# ADSR_Waveform_v1_05.net
KiCad netlist of a schematic drawn in EAGLE
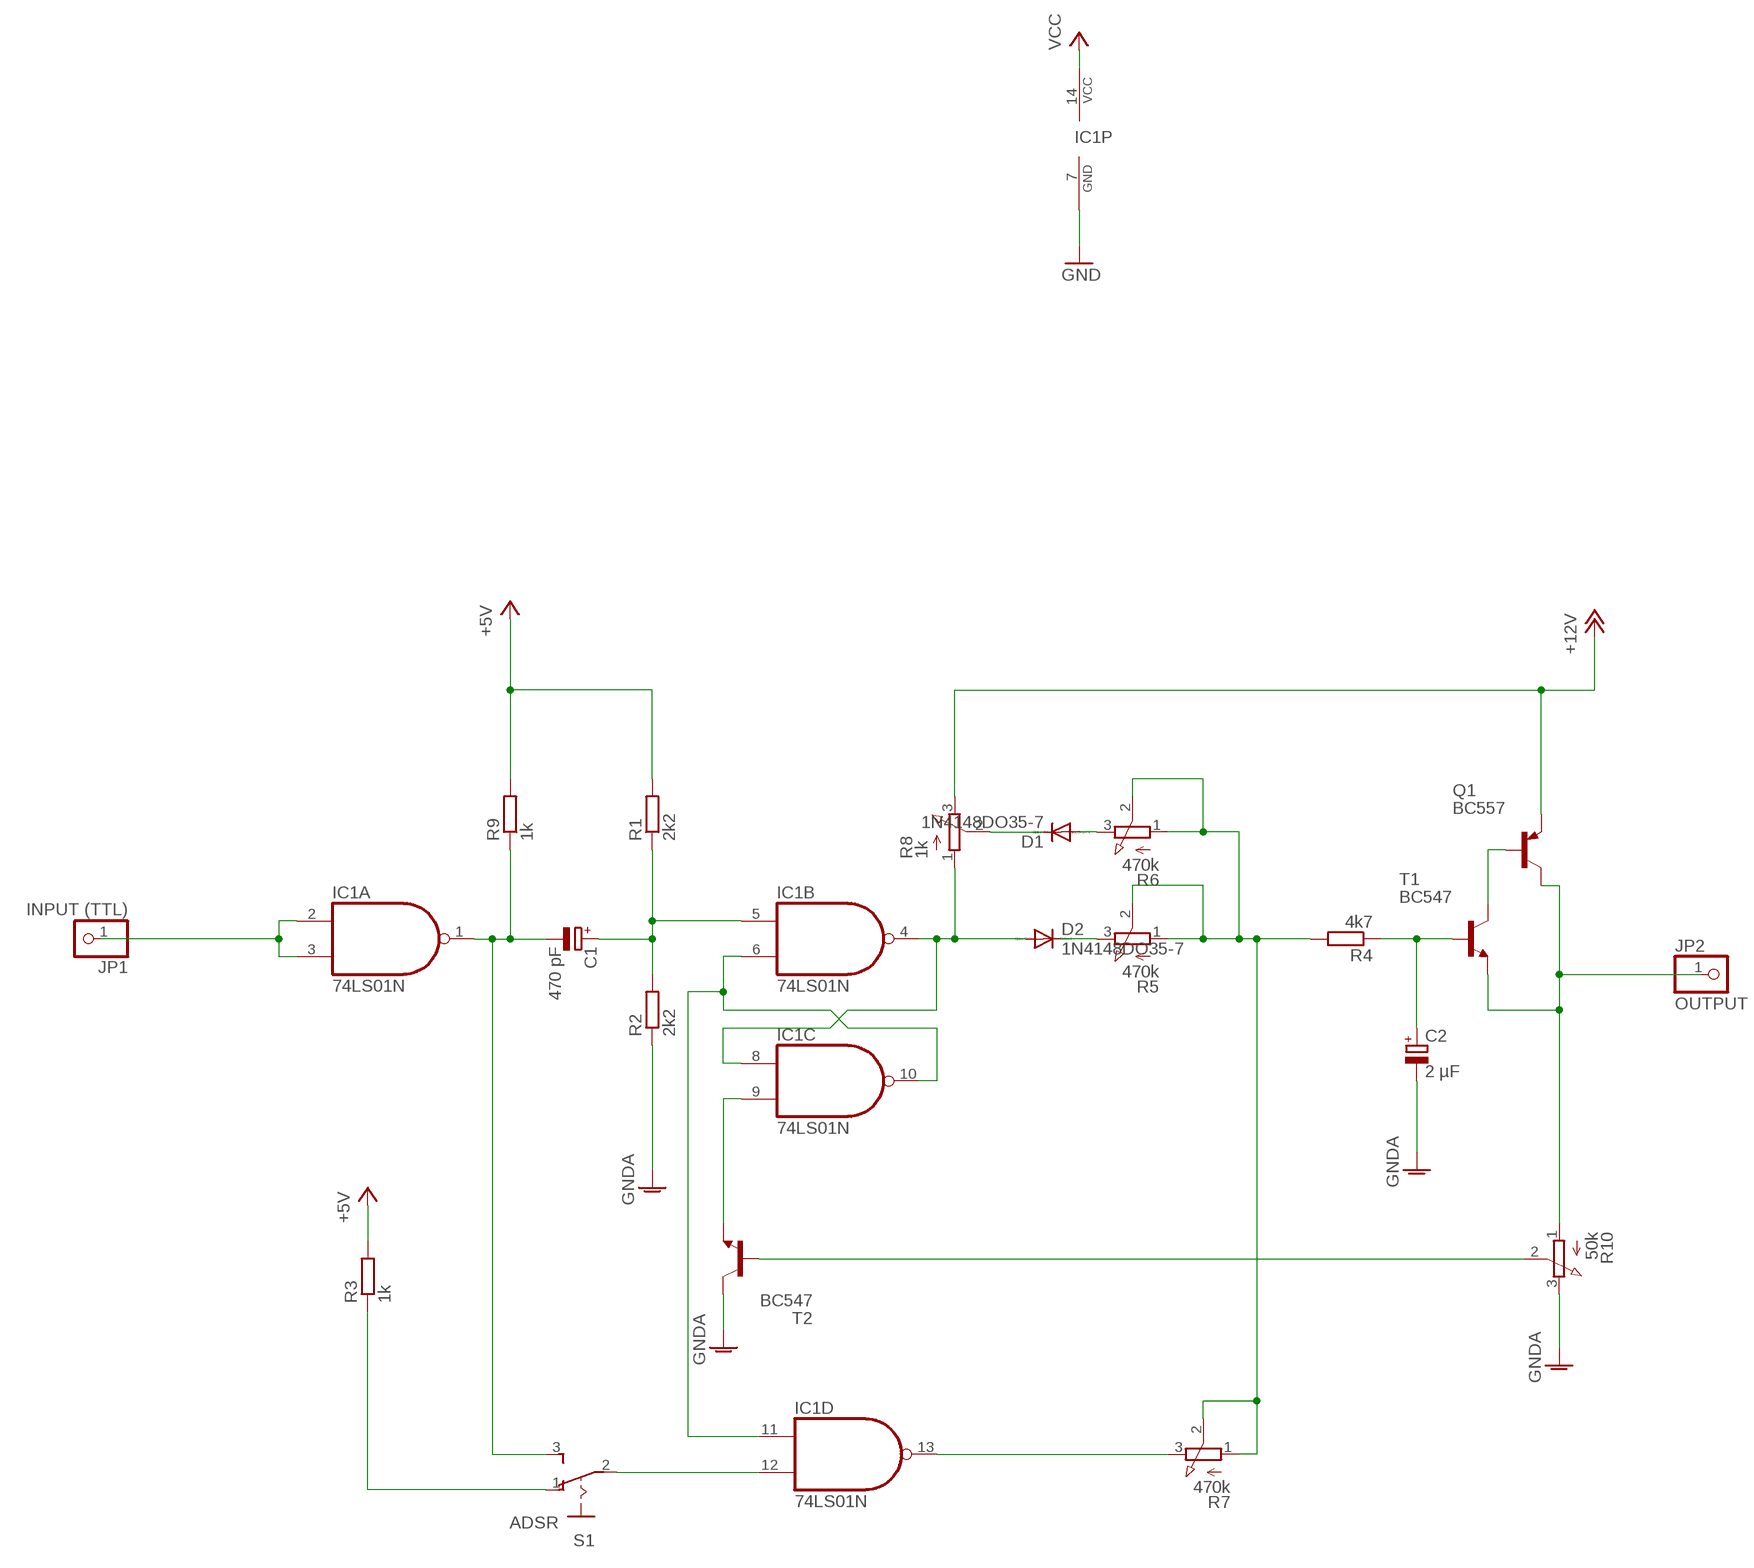
[diagram p0: schematic, sheet 1]

(export (version "E")
  (design (tool "Eeschema 10.0.6"))
  (components
    (comp (ref "C1")
      (value "470 pF")
      (footprint "eagle-import:E5-5")
      (libsource (lib "eagle-import") (part "CPOL-EUE5-5"))
    )
    (comp (ref "C2")
      (value "2 µF")
      (footprint "eagle-import:E5-5")
      (libsource (lib "eagle-import") (part "CPOL-EUE5-5"))
    )
    (comp (ref "D1")
      (value "1N4148DO35-7")
      (footprint "eagle-import:DO35-7")
      (libsource (lib "eagle-import") (part "1N4148DO35-7"))
    )
    (comp (ref "D2")
      (value "1N4148DO35-7")
      (footprint "eagle-import:DO35-7")
      (libsource (lib "eagle-import") (part "1N4148DO35-7"))
    )
    (comp (ref "IC1")
      (value "74LS01N")
      (footprint "eagle-import:DIL14")
      (libsource (lib "eagle-import") (part "7401NLS"))
    )
    (comp (ref "JP1")
      (value "INPUT (TTL)")
      (footprint "eagle-import:1X01")
      (libsource (lib "eagle-import") (part "PINHD-1X1"))
    )
    (comp (ref "JP2")
      (value "OUTPUT")
      (footprint "eagle-import:1X01")
      (libsource (lib "eagle-import") (part "PINHD-1X1"))
    )
    (comp (ref "Q1")
      (value "BC557")
      (footprint "eagle-import:TO92")
      (libsource (lib "eagle-import") (part "BC557"))
    )
    (comp (ref "R1")
      (value "2k2")
      (footprint "eagle-import:0204_5")
      (libsource (lib "eagle-import") (part "R-EU_0204/5"))
    )
    (comp (ref "R2")
      (value "2k2")
      (footprint "eagle-import:0204_5")
      (libsource (lib "eagle-import") (part "R-EU_0204/5"))
    )
    (comp (ref "R3")
      (value "1k")
      (footprint "eagle-import:0204_5")
      (libsource (lib "eagle-import") (part "R-EU_0204/5"))
    )
    (comp (ref "R4")
      (value "4k7")
      (footprint "eagle-import:0204_5")
      (libsource (lib "eagle-import") (part "R-EU_0204/5"))
    )
    (comp (ref "R5")
      (value "470k")
      (footprint "eagle-import:3RP_1610N")
      (libsource (lib "eagle-import") (part "3RP/1610N"))
    )
    (comp (ref "R6")
      (value "470k")
      (footprint "eagle-import:3RP_1610N")
      (libsource (lib "eagle-import") (part "3RP/1610N"))
    )
    (comp (ref "R7")
      (value "470k")
      (footprint "eagle-import:3RP_1610N")
      (libsource (lib "eagle-import") (part "3RP/1610N"))
    )
    (comp (ref "R8")
      (value "1k")
      (footprint "eagle-import:3RP_1610N")
      (libsource (lib "eagle-import") (part "3RP/1610N"))
    )
    (comp (ref "R9")
      (value "1k")
      (footprint "eagle-import:0204_5")
      (libsource (lib "eagle-import") (part "R-EU_0204/5"))
    )
    (comp (ref "R10")
      (value "50k")
      (footprint "eagle-import:3RP_1610N")
      (libsource (lib "eagle-import") (part "3RP/1610N"))
    )
    (comp (ref "S1")
      (value "ADSR")
      (footprint "eagle-import:255SB")
      (libsource (lib "eagle-import") (part "255SB"))
    )
    (comp (ref "T1")
      (value "BC547")
      (footprint "eagle-import:TO92")
      (libsource (lib "eagle-import") (part "BC547"))
    )
    (comp (ref "T2")
      (value "BC547")
      (footprint "eagle-import:TO92")
      (libsource (lib "eagle-import") (part "BC547"))
    )
  )
  (nets
    (net (code "1") (name "+5V") (class "Default")
      (node (ref "R1") (pin "2") (pinfunction "2_2") (pintype "passive"))
      (node (ref "R3") (pin "2") (pinfunction "2_2") (pintype "passive"))
      (node (ref "R9") (pin "2") (pinfunction "2_2") (pintype "passive"))
    )
    (net (code "2") (name "+12V") (class "Default")
      (node (ref "Q1") (pin "1") (pinfunction "E_1") (pintype "passive"))
      (node (ref "R8") (pin "3") (pinfunction "E_3") (pintype "passive"))
    )
    (net (code "3") (name "GND") (class "Default")
      (node (ref "IC1") (pin "7") (pinfunction "GND_7") (pintype "power_in"))
    )
    (net (code "4") (name "GNDA") (class "Default")
      (node (ref "C2") (pin "-") (pinfunction "-_-") (pintype "passive"))
      (node (ref "R10") (pin "3") (pinfunction "E_3") (pintype "passive"))
      (node (ref "R2") (pin "1") (pinfunction "1_1") (pintype "passive"))
      (node (ref "T2") (pin "3") (pinfunction "C_3") (pintype "passive"))
    )
    (net (code "5") (name "Net-(IC1A-I0)") (class "Default")
      (node (ref "IC1") (pin "2") (pinfunction "I0_2") (pintype "input"))
      (node (ref "IC1") (pin "3") (pinfunction "I1_3") (pintype "input"))
      (node (ref "JP1") (pin "1") (pinfunction "1_1") (pintype "passive"))
    )
    (net (code "6") (name "Net-(IC1A-O)") (class "Default")
      (node (ref "C1") (pin "-") (pinfunction "-_-") (pintype "passive"))
      (node (ref "IC1") (pin "1") (pinfunction "O_1") (pintype "open_collector"))
      (node (ref "R9") (pin "1") (pinfunction "1_1") (pintype "passive"))
      (node (ref "S1") (pin "3") (pinfunction "S_3") (pintype "passive"))
    )
    (net (code "7") (name "Net-(IC1B-I0)") (class "Default")
      (node (ref "C1") (pin "+") (pinfunction "+_+") (pintype "passive"))
      (node (ref "IC1") (pin "5") (pinfunction "I0_5") (pintype "input"))
      (node (ref "R1") (pin "1") (pinfunction "1_1") (pintype "passive"))
      (node (ref "R2") (pin "2") (pinfunction "2_2") (pintype "passive"))
    )
    (net (code "8") (name "Net-(IC1B-I1)") (class "Default")
      (node (ref "IC1") (pin "10") (pinfunction "O_10") (pintype "open_collector"))
      (node (ref "IC1") (pin "11") (pinfunction "I0_11") (pintype "input"))
      (node (ref "IC1") (pin "6") (pinfunction "I1_6") (pintype "input"))
    )
    (net (code "9") (name "Net-(IC1B-O)") (class "Default")
      (node (ref "D2") (pin "A") (pinfunction "A_A") (pintype "passive"))
      (node (ref "IC1") (pin "4") (pinfunction "O_4") (pintype "open_collector"))
      (node (ref "IC1") (pin "8") (pinfunction "I0_8") (pintype "input"))
      (node (ref "R8") (pin "1") (pinfunction "A_1") (pintype "passive"))
    )
    (net (code "10") (name "Net-(IC1C-I1)") (class "Default")
      (node (ref "IC1") (pin "9") (pinfunction "I1_9") (pintype "input"))
      (node (ref "T2") (pin "1") (pinfunction "E_1") (pintype "passive"))
    )
    (net (code "11") (name "Net-(IC1D-I1)") (class "Default")
      (node (ref "IC1") (pin "12") (pinfunction "I1_12") (pintype "input"))
      (node (ref "S1") (pin "2") (pinfunction "P_2") (pintype "passive"))
    )
    (net (code "12") (name "Net-(IC1D-O)") (class "Default")
      (node (ref "IC1") (pin "13") (pinfunction "O_13") (pintype "open_collector"))
      (node (ref "R7") (pin "3") (pinfunction "E_3") (pintype "passive"))
    )
    (net (code "13") (name "Net-(Q1-B)") (class "Default")
      (node (ref "Q1") (pin "2") (pinfunction "B_2") (pintype "passive"))
      (node (ref "T1") (pin "3") (pinfunction "C_3") (pintype "passive"))
    )
    (net (code "14") (name "Net-(Q1-C)") (class "Default")
      (node (ref "JP2") (pin "1") (pinfunction "1_1") (pintype "passive"))
      (node (ref "Q1") (pin "3") (pinfunction "C_3") (pintype "passive"))
      (node (ref "R10") (pin "1") (pinfunction "A_1") (pintype "passive"))
      (node (ref "T1") (pin "1") (pinfunction "E_1") (pintype "passive"))
    )
    (net (code "15") (name "Net-(R5-A)") (class "Default")
      (node (ref "R4") (pin "2") (pinfunction "2_2") (pintype "passive"))
      (node (ref "R5") (pin "1") (pinfunction "A_1") (pintype "passive"))
      (node (ref "R5") (pin "2") (pinfunction "S_2") (pintype "passive"))
      (node (ref "R6") (pin "1") (pinfunction "A_1") (pintype "passive"))
      (node (ref "R6") (pin "2") (pinfunction "S_2") (pintype "passive"))
      (node (ref "R7") (pin "1") (pinfunction "A_1") (pintype "passive"))
      (node (ref "R7") (pin "2") (pinfunction "S_2") (pintype "passive"))
    )
    (net (code "16") (name "Net-(R5-E)") (class "Default")
      (node (ref "D2") (pin "C") (pinfunction "C_C") (pintype "passive"))
      (node (ref "R5") (pin "3") (pinfunction "E_3") (pintype "passive"))
    )
    (net (code "17") (name "Net-(R6-E)") (class "Default")
      (node (ref "D1") (pin "A") (pinfunction "A_A") (pintype "passive"))
      (node (ref "R6") (pin "3") (pinfunction "E_3") (pintype "passive"))
    )
    (net (code "18") (name "Net-(R8-S)") (class "Default")
      (node (ref "D1") (pin "C") (pinfunction "C_C") (pintype "passive"))
      (node (ref "R8") (pin "2") (pinfunction "S_2") (pintype "passive"))
    )
    (net (code "19") (name "Net-(R10-S)") (class "Default")
      (node (ref "R10") (pin "2") (pinfunction "S_2") (pintype "passive"))
      (node (ref "T2") (pin "2") (pinfunction "B_2") (pintype "passive"))
    )
    (net (code "20") (name "Net-(S1-O)") (class "Default")
      (node (ref "R3") (pin "1") (pinfunction "1_1") (pintype "passive"))
      (node (ref "S1") (pin "1") (pinfunction "O_1") (pintype "passive"))
    )
    (net (code "21") (name "Net-(T1-B)") (class "Default")
      (node (ref "C2") (pin "+") (pinfunction "+_+") (pintype "passive"))
      (node (ref "R4") (pin "1") (pinfunction "1_1") (pintype "passive"))
      (node (ref "T1") (pin "2") (pinfunction "B_2") (pintype "passive"))
    )
    (net (code "22") (name "VCC") (class "Default")
      (node (ref "IC1") (pin "14") (pinfunction "VCC_14") (pintype "power_in"))
    )
  )
)
